# QCopterRC_LED_Sch.net
KiCad netlist of a schematic drawn in Altium Designer
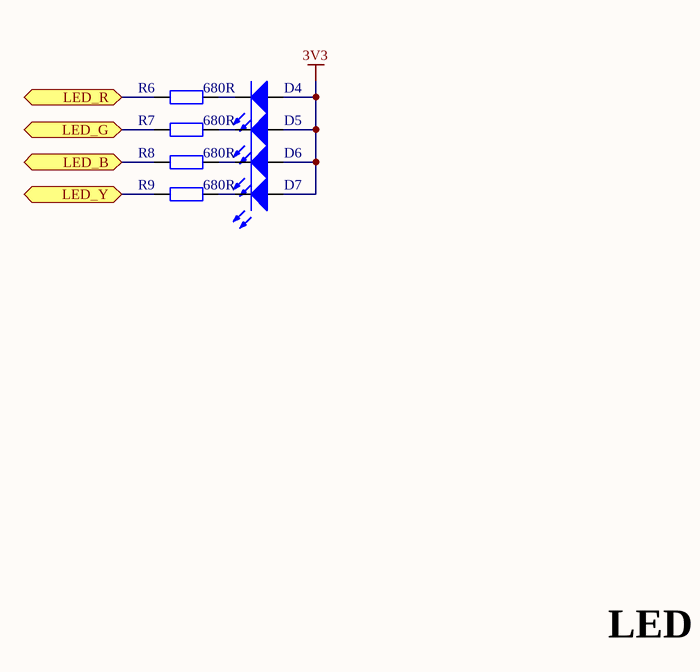
[diagram p0: QCopterRC_LED_Sch.SchDoc]

(export (version "E")
  (design (tool "Eeschema 10.0.6"))
  (components
    (comp (ref "D4")
      (value "LED_0603_RED")
      (footprint "PCB_Active:LED_0603_RED")
      (description "LED")
      (libsource (lib "SCH_Active") (part "LED_0603_RED"))
    )
    (comp (ref "D5")
      (value "LED_0603_GREEN")
      (footprint "PCB_Active:LED_0603_GREEN")
      (description "LED")
      (libsource (lib "SCH_Active") (part "LED_0603_GREEN"))
    )
    (comp (ref "D6")
      (value "LED_0603_BLUE")
      (footprint "PCB_Active:LED_0603_BLUE")
      (description "LED")
      (libsource (lib "SCH_Active") (part "LED_0603_BLUE"))
    )
    (comp (ref "D7")
      (value "LED_0603_YELLOW")
      (footprint "PCB_Active:LED_0603_YELLOW")
      (description "LED")
      (libsource (lib "SCH_Active") (part "LED_0603_YELLOW"))
    )
    (comp (ref "R6")
      (value "680R")
      (footprint "PCB_Passive:RES_0603")
      (description "Resistor")
      (fields (field (name "Comment") "Res_0603"))
      (libsource (lib "SCH_Passive") (part "Res_0603"))
    )
    (comp (ref "R7")
      (value "680R")
      (footprint "PCB_Passive:RES_0603")
      (description "Resistor")
      (fields (field (name "Comment") "Res_0603"))
      (libsource (lib "SCH_Passive") (part "Res_0603"))
    )
    (comp (ref "R8")
      (value "680R")
      (footprint "PCB_Passive:RES_0603")
      (description "Resistor")
      (fields (field (name "Comment") "Res_0603"))
      (libsource (lib "SCH_Passive") (part "Res_0603"))
    )
    (comp (ref "R9")
      (value "680R")
      (footprint "PCB_Passive:RES_0603")
      (description "Resistor")
      (fields (field (name "Comment") "Res_0603"))
      (libsource (lib "SCH_Passive") (part "Res_0603"))
    )
  )
  (nets
    (net (code "1") (name "/LED_B") (class "Default")
      (node (ref "R8") (pin "1") (pinfunction "1_1") (pintype "passive"))
    )
    (net (code "2") (name "/LED_G") (class "Default")
      (node (ref "R7") (pin "1") (pinfunction "1_1") (pintype "passive"))
    )
    (net (code "3") (name "/LED_R") (class "Default")
      (node (ref "R6") (pin "1") (pinfunction "1_1") (pintype "passive"))
    )
    (net (code "4") (name "/LED_Y") (class "Default")
      (node (ref "R9") (pin "1") (pinfunction "1_1") (pintype "passive"))
    )
    (net (code "5") (name "3V3") (class "Default")
      (node (ref "D4") (pin "1") (pinfunction "A_1") (pintype "passive"))
      (node (ref "D5") (pin "1") (pinfunction "A_1") (pintype "passive"))
      (node (ref "D6") (pin "1") (pinfunction "A_1") (pintype "passive"))
      (node (ref "D7") (pin "1") (pinfunction "A_1") (pintype "passive"))
    )
    (net (code "6") (name "Net-(D4-K)") (class "Default")
      (node (ref "D4") (pin "2") (pinfunction "K_2") (pintype "passive"))
      (node (ref "R6") (pin "2") (pinfunction "2_2") (pintype "passive"))
    )
    (net (code "7") (name "Net-(D5-K)") (class "Default")
      (node (ref "D5") (pin "2") (pinfunction "K_2") (pintype "passive"))
      (node (ref "R7") (pin "2") (pinfunction "2_2") (pintype "passive"))
    )
    (net (code "8") (name "Net-(D6-K)") (class "Default")
      (node (ref "D6") (pin "2") (pinfunction "K_2") (pintype "passive"))
      (node (ref "R8") (pin "2") (pinfunction "2_2") (pintype "passive"))
    )
    (net (code "9") (name "Net-(D7-K)") (class "Default")
      (node (ref "D7") (pin "2") (pinfunction "K_2") (pintype "passive"))
      (node (ref "R9") (pin "2") (pinfunction "2_2") (pintype "passive"))
    )
  )
)
